# md-01.net
KiCad netlist of a schematic drawn in EAGLE
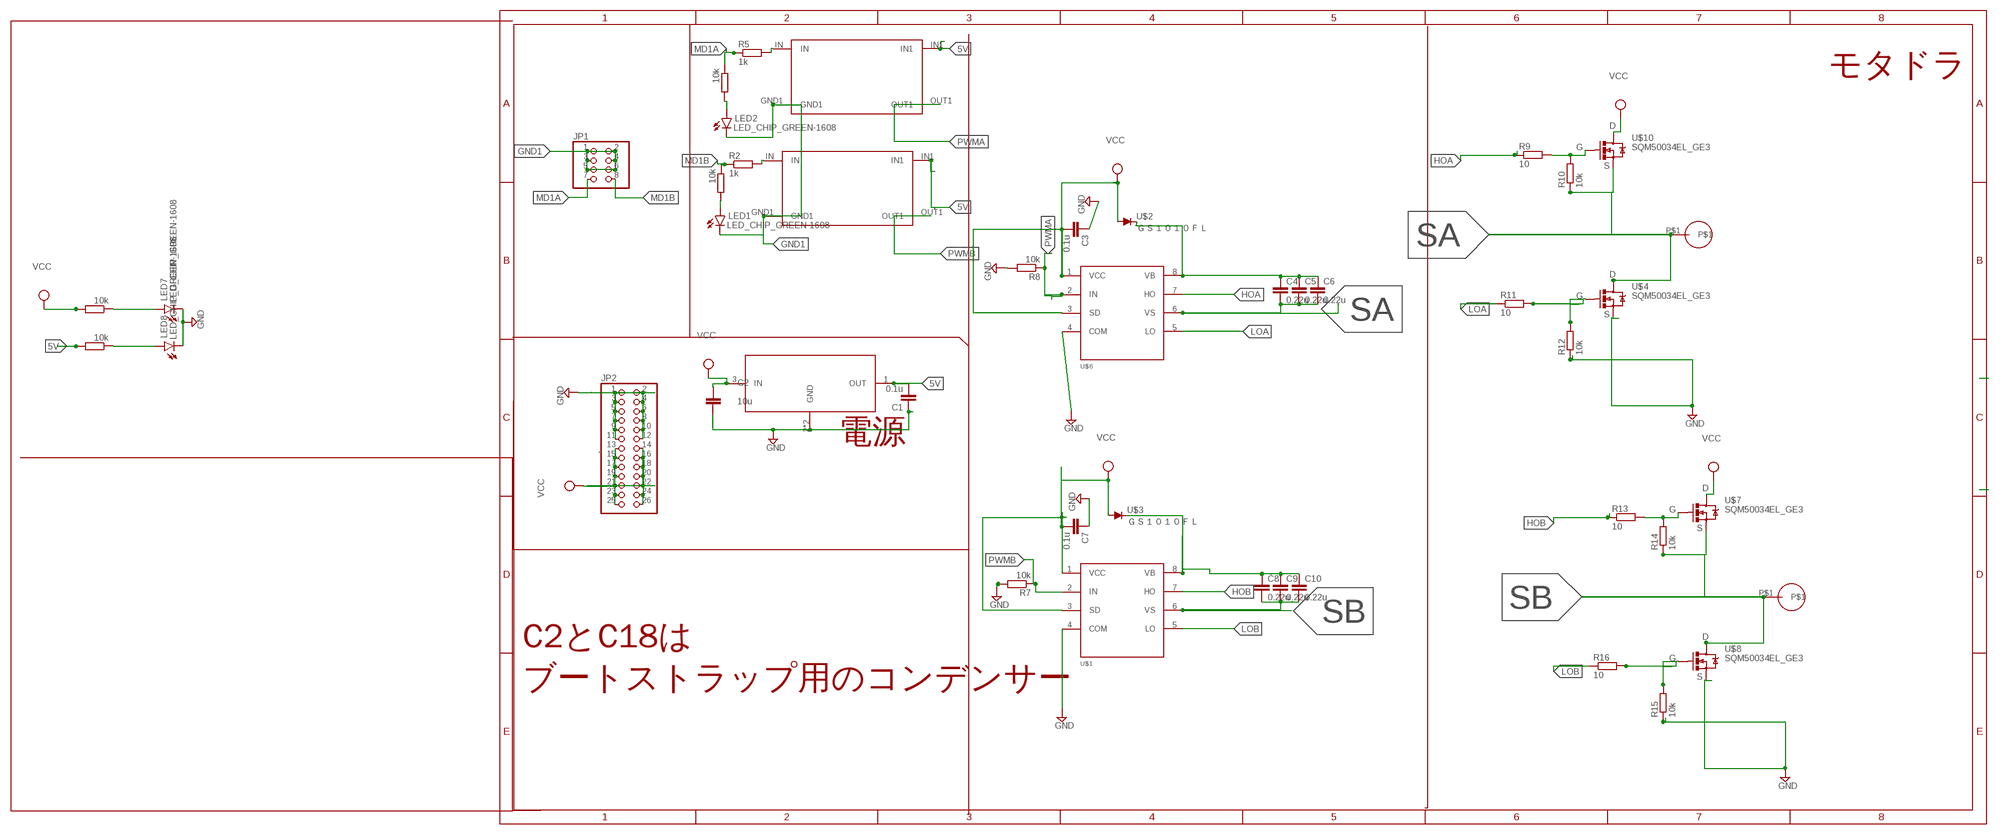
[diagram p0: schematic, sheet 1]

(export (version "E")
  (design (tool "Eeschema 10.0.6"))
  (components
    (comp (ref "C1")
      (value "0.1u")
      (footprint "eagle-import:C0603")
      (libsource (lib "eagle-import") (part "C-EUC0603"))
    )
    (comp (ref "C2")
      (value "10u")
      (footprint "eagle-import:C0805")
      (libsource (lib "eagle-import") (part "C-EUC0805"))
    )
    (comp (ref "C3")
      (value "0.1u")
      (footprint "eagle-import:C0603")
      (libsource (lib "eagle-import") (part "C-EUC0603"))
    )
    (comp (ref "C4")
      (value "0.22u")
      (footprint "eagle-import:C2012")
      (libsource (lib "eagle-import") (part "C-EUC2012"))
    )
    (comp (ref "C5")
      (value "0.22u")
      (footprint "eagle-import:C2012")
      (libsource (lib "eagle-import") (part "C-EUC2012"))
    )
    (comp (ref "C6")
      (value "0.22u")
      (footprint "eagle-import:C2012")
      (libsource (lib "eagle-import") (part "C-EUC2012"))
    )
    (comp (ref "C7")
      (value "0.1u")
      (footprint "eagle-import:C0603")
      (libsource (lib "eagle-import") (part "C-EUC0603"))
    )
    (comp (ref "C8")
      (value "0.22u")
      (footprint "eagle-import:C2012")
      (libsource (lib "eagle-import") (part "C-EUC2012"))
    )
    (comp (ref "C9")
      (value "0.22u")
      (footprint "eagle-import:C2012")
      (libsource (lib "eagle-import") (part "C-EUC2012"))
    )
    (comp (ref "C10")
      (value "0.22u")
      (footprint "eagle-import:C2012")
      (libsource (lib "eagle-import") (part "C-EUC2012"))
    )
    (comp (ref "JP1")
      (value "PINHD-2X4/90")
      (footprint "eagle-import:2X04_90")
      (libsource (lib "eagle-import") (part "PINHD-2X4/90"))
    )
    (comp (ref "JP2")
      (value "PINHD-2X13/90")
      (footprint "eagle-import:2X13_90")
      (libsource (lib "eagle-import") (part "PINHD-2X13/90"))
    )
    (comp (ref "LED1")
      (value "LED_CHIP_GREEN-1608")
      (footprint "eagle-import:LEDC1608X39N_G")
      (libsource (lib "eagle-import") (part "LED_CHIPGREEN-1608_"))
    )
    (comp (ref "LED2")
      (value "LED_CHIP_GREEN-1608")
      (footprint "eagle-import:LEDC1608X39N_G")
      (libsource (lib "eagle-import") (part "LED_CHIPGREEN-1608_"))
    )
    (comp (ref "LED7")
      (value "LED_CHIP_GREEN-1608")
      (footprint "eagle-import:LEDC1608X39N_G")
      (libsource (lib "eagle-import") (part "LED_CHIPGREEN-1608_"))
    )
    (comp (ref "LED8")
      (value "LED_CHIP_GREEN-1608")
      (footprint "eagle-import:LEDC1608X39N_G")
      (libsource (lib "eagle-import") (part "LED_CHIPGREEN-1608_"))
    )
    (comp (ref "R1")
      (value "10k")
      (footprint "eagle-import:R0603")
      (libsource (lib "eagle-import") (part "R-EU_R0603"))
    )
    (comp (ref "R2")
      (value "1k")
      (footprint "eagle-import:R0603")
      (libsource (lib "eagle-import") (part "R-EU_R0603"))
    )
    (comp (ref "R4")
      (value "10k")
      (footprint "eagle-import:R0603")
      (libsource (lib "eagle-import") (part "R-EU_R0603"))
    )
    (comp (ref "R5")
      (value "1k")
      (footprint "eagle-import:R0603")
      (libsource (lib "eagle-import") (part "R-EU_R0603"))
    )
    (comp (ref "R7")
      (value "10k")
      (footprint "eagle-import:R0603")
      (libsource (lib "eagle-import") (part "R-EU_R0603"))
    )
    (comp (ref "R8")
      (value "10k")
      (footprint "eagle-import:R0603")
      (libsource (lib "eagle-import") (part "R-EU_R0603"))
    )
    (comp (ref "R9")
      (value "10")
      (footprint "eagle-import:R0603")
      (libsource (lib "eagle-import") (part "R-EU_R0603"))
    )
    (comp (ref "R10")
      (value "10k")
      (footprint "eagle-import:R0603")
      (libsource (lib "eagle-import") (part "R-EU_R0603"))
    )
    (comp (ref "R11")
      (value "10")
      (footprint "eagle-import:R0603")
      (libsource (lib "eagle-import") (part "R-EU_R0603"))
    )
    (comp (ref "R12")
      (value "10k")
      (footprint "eagle-import:R0603")
      (libsource (lib "eagle-import") (part "R-EU_R0603"))
    )
    (comp (ref "R13")
      (value "10")
      (footprint "eagle-import:R0603")
      (libsource (lib "eagle-import") (part "R-EU_R0603"))
    )
    (comp (ref "R14")
      (value "10k")
      (footprint "eagle-import:R0603")
      (libsource (lib "eagle-import") (part "R-EU_R0603"))
    )
    (comp (ref "R15")
      (value "10k")
      (footprint "eagle-import:R0603")
      (libsource (lib "eagle-import") (part "R-EU_R0603"))
    )
    (comp (ref "R16")
      (value "10")
      (footprint "eagle-import:R0603")
      (libsource (lib "eagle-import") (part "R-EU_R0603"))
    )
    (comp (ref "R17")
      (value "10k")
      (footprint "eagle-import:R0603")
      (libsource (lib "eagle-import") (part "R-EU_R0603"))
    )
    (comp (ref "R19")
      (value "10k")
      (footprint "eagle-import:R0603")
      (libsource (lib "eagle-import") (part "R-EU_R0603"))
    )
    (comp (ref "U$1")
      (value "ＩＲ２１０４ＳＴＲＰＢＦ")
      (footprint "eagle-import:SOIC-8")
      (libsource (lib "eagle-import") (part "ＩＲ２１０４ＳＴＲＰＢＦ"))
    )
    (comp (ref "U$2")
      (value "ＧＳ１０１０ＦＬ")
      (footprint "eagle-import:DIODE_SOD-123FL")
      (libsource (lib "eagle-import") (part "ＧＳ１０１０ＦＬ"))
    )
    (comp (ref "U$3")
      (value "ＧＳ１０１０ＦＬ")
      (footprint "eagle-import:DIODE_SOD-123FL")
      (libsource (lib "eagle-import") (part "ＧＳ１０１０ＦＬ"))
    )
    (comp (ref "U$4")
      (value "SQM50034EL_GE3")
      (footprint "eagle-import:TO-263_D2PAK")
      (libsource (lib "eagle-import") (part "SQM50034EL_GE3"))
    )
    (comp (ref "U$5")
      (value "PV-3")
      (footprint "eagle-import:PV-3")
      (libsource (lib "eagle-import") (part "PV-3"))
    )
    (comp (ref "U$6")
      (value "ＩＲ２１０４ＳＴＲＰＢＦ")
      (footprint "eagle-import:SOIC-8")
      (libsource (lib "eagle-import") (part "ＩＲ２１０４ＳＴＲＰＢＦ"))
    )
    (comp (ref "U$7")
      (value "SQM50034EL_GE3")
      (footprint "eagle-import:TO-263_D2PAK")
      (libsource (lib "eagle-import") (part "SQM50034EL_GE3"))
    )
    (comp (ref "U$8")
      (value "SQM50034EL_GE3")
      (footprint "eagle-import:TO-263_D2PAK")
      (libsource (lib "eagle-import") (part "SQM50034EL_GE3"))
    )
    (comp (ref "U$9")
      (value "PV-3")
      (footprint "eagle-import:PV-3")
      (libsource (lib "eagle-import") (part "PV-3"))
    )
    (comp (ref "U$10")
      (value "SQM50034EL_GE3")
      (footprint "eagle-import:TO-263_D2PAK")
      (libsource (lib "eagle-import") (part "SQM50034EL_GE3"))
    )
    (comp (ref "U$11")
      (value "ＴＬＰ２９３（ＧＢ）")
      (footprint "eagle-import:MINI-FLAT-4")
      (libsource (lib "eagle-import") (part "ＴＬＰ２９３（ＧＢ）"))
    )
    (comp (ref "U$12")
      (value "ＴＬＰ２９３（ＧＢ）")
      (footprint "eagle-import:MINI-FLAT-4")
      (libsource (lib "eagle-import") (part "ＴＬＰ２９３（ＧＢ）"))
    )
    (comp (ref "U$13")
      (value "NJM78L05SU3")
      (footprint "eagle-import:SOT-89")
      (libsource (lib "eagle-import") (part "NJM78L05SU3"))
    )
  )
  (nets
    (net (code "1") (name "5V") (class "Default")
      (node (ref "C1") (pin "2") (pinfunction "2_2") (pintype "passive"))
      (node (ref "R19") (pin "2") (pinfunction "2_2") (pintype "passive"))
      (node (ref "U$11") (pin "IN1") (pinfunction "IN1_IN1") (pintype "bidirectional"))
      (node (ref "U$12") (pin "IN1") (pinfunction "IN1_IN1") (pintype "bidirectional"))
      (node (ref "U$13") (pin "1") (pinfunction "OUT_1") (pintype "bidirectional"))
    )
    (net (code "2") (name "GND") (class "Default")
      (node (ref "C1") (pin "1") (pinfunction "1_1") (pintype "passive"))
      (node (ref "C2") (pin "2") (pinfunction "2_2") (pintype "passive"))
      (node (ref "C3") (pin "1") (pinfunction "1_1") (pintype "passive"))
      (node (ref "C7") (pin "1") (pinfunction "1_1") (pintype "passive"))
      (node (ref "JP2") (pin "1") (pinfunction "1_1") (pintype "passive"))
      (node (ref "JP2") (pin "10") (pinfunction "10_10") (pintype "passive"))
      (node (ref "JP2") (pin "11") (pinfunction "11_11") (pintype "passive"))
      (node (ref "JP2") (pin "12") (pinfunction "12_12") (pintype "passive"))
      (node (ref "JP2") (pin "2") (pinfunction "2_2") (pintype "passive"))
      (node (ref "JP2") (pin "3") (pinfunction "3_3") (pintype "passive"))
      (node (ref "JP2") (pin "4") (pinfunction "4_4") (pintype "passive"))
      (node (ref "JP2") (pin "5") (pinfunction "5_5") (pintype "passive"))
      (node (ref "JP2") (pin "6") (pinfunction "6_6") (pintype "passive"))
      (node (ref "JP2") (pin "7") (pinfunction "7_7") (pintype "passive"))
      (node (ref "JP2") (pin "8") (pinfunction "8_8") (pintype "passive"))
      (node (ref "JP2") (pin "9") (pinfunction "9_9") (pintype "passive"))
      (node (ref "LED7") (pin "1") (pinfunction "C_1") (pintype "passive"))
      (node (ref "LED8") (pin "1") (pinfunction "C_1") (pintype "passive"))
      (node (ref "R12") (pin "1") (pinfunction "1_1") (pintype "passive"))
      (node (ref "R15") (pin "1") (pinfunction "1_1") (pintype "passive"))
      (node (ref "R7") (pin "2") (pinfunction "2_2") (pintype "passive"))
      (node (ref "R8") (pin "2") (pinfunction "2_2") (pintype "passive"))
      (node (ref "U$1") (pin "4") (pinfunction "COM_4") (pintype "bidirectional"))
      (node (ref "U$13") (pin "2") (pinfunction "GND_2") (pintype "bidirectional"))
      (node (ref "U$13") (pin "4") (pinfunction "GND_4") (pintype "bidirectional"))
      (node (ref "U$4") (pin "S") (pinfunction "S_S") (pintype "passive"))
      (node (ref "U$6") (pin "4") (pinfunction "COM_4") (pintype "bidirectional"))
      (node (ref "U$8") (pin "S") (pinfunction "S_S") (pintype "passive"))
    )
    (net (code "3") (name "GND1") (class "Default")
      (node (ref "JP1") (pin "1") (pinfunction "1_1") (pintype "passive"))
      (node (ref "JP1") (pin "2") (pinfunction "2_2") (pintype "passive"))
      (node (ref "JP1") (pin "3") (pinfunction "3_3") (pintype "passive"))
      (node (ref "JP1") (pin "4") (pinfunction "4_4") (pintype "passive"))
      (node (ref "JP1") (pin "5") (pinfunction "5_5") (pintype "passive"))
      (node (ref "JP1") (pin "6") (pinfunction "6_6") (pintype "passive"))
      (node (ref "LED1") (pin "1") (pinfunction "C_1") (pintype "passive"))
      (node (ref "LED2") (pin "1") (pinfunction "C_1") (pintype "passive"))
      (node (ref "U$11") (pin "GND1") (pinfunction "GND1_GND1") (pintype "bidirectional"))
      (node (ref "U$12") (pin "GND1") (pinfunction "GND1_GND1") (pintype "bidirectional"))
    )
    (net (code "4") (name "HOA") (class "Default")
      (node (ref "R9") (pin "1") (pinfunction "1_1") (pintype "passive"))
      (node (ref "U$6") (pin "7") (pinfunction "HO_7") (pintype "bidirectional"))
    )
    (net (code "5") (name "HOB") (class "Default")
      (node (ref "R13") (pin "1") (pinfunction "1_1") (pintype "passive"))
      (node (ref "U$1") (pin "7") (pinfunction "HO_7") (pintype "bidirectional"))
    )
    (net (code "6") (name "LOA") (class "Default")
      (node (ref "R11") (pin "1") (pinfunction "1_1") (pintype "passive"))
      (node (ref "U$6") (pin "5") (pinfunction "LO_5") (pintype "bidirectional"))
    )
    (net (code "7") (name "LOB") (class "Default")
      (node (ref "R16") (pin "1") (pinfunction "1_1") (pintype "passive"))
      (node (ref "U$1") (pin "5") (pinfunction "LO_5") (pintype "bidirectional"))
    )
    (net (code "8") (name "MD1A") (class "Default")
      (node (ref "JP1") (pin "7") (pinfunction "7_7") (pintype "passive"))
      (node (ref "R4") (pin "1") (pinfunction "1_1") (pintype "passive"))
      (node (ref "R5") (pin "1") (pinfunction "1_1") (pintype "passive"))
    )
    (net (code "9") (name "MD1B") (class "Default")
      (node (ref "JP1") (pin "8") (pinfunction "8_8") (pintype "passive"))
      (node (ref "R1") (pin "1") (pinfunction "1_1") (pintype "passive"))
      (node (ref "R2") (pin "1") (pinfunction "1_1") (pintype "passive"))
    )
    (net (code "10") (name "Net-(LED1-A)") (class "Default")
      (node (ref "LED1") (pin "2") (pinfunction "A_2") (pintype "passive"))
      (node (ref "R1") (pin "2") (pinfunction "2_2") (pintype "passive"))
    )
    (net (code "11") (name "Net-(LED2-A)") (class "Default")
      (node (ref "LED2") (pin "2") (pinfunction "A_2") (pintype "passive"))
      (node (ref "R4") (pin "2") (pinfunction "2_2") (pintype "passive"))
    )
    (net (code "12") (name "Net-(LED7-A)") (class "Default")
      (node (ref "LED7") (pin "2") (pinfunction "A_2") (pintype "passive"))
      (node (ref "R17") (pin "1") (pinfunction "1_1") (pintype "passive"))
    )
    (net (code "13") (name "Net-(LED8-A)") (class "Default")
      (node (ref "LED8") (pin "2") (pinfunction "A_2") (pintype "passive"))
      (node (ref "R19") (pin "1") (pinfunction "1_1") (pintype "passive"))
    )
    (net (code "14") (name "Net-(R2-Pad2)") (class "Default")
      (node (ref "R2") (pin "2") (pinfunction "2_2") (pintype "passive"))
      (node (ref "U$12") (pin "IN") (pinfunction "IN_IN") (pintype "bidirectional"))
    )
    (net (code "15") (name "Net-(R5-Pad2)") (class "Default")
      (node (ref "R5") (pin "2") (pinfunction "2_2") (pintype "passive"))
      (node (ref "U$11") (pin "IN") (pinfunction "IN_IN") (pintype "bidirectional"))
    )
    (net (code "16") (name "Net-(R10-Pad2)") (class "Default")
      (node (ref "R10") (pin "2") (pinfunction "2_2") (pintype "passive"))
      (node (ref "R9") (pin "2") (pinfunction "2_2") (pintype "passive"))
      (node (ref "U$10") (pin "G") (pinfunction "G_G") (pintype "passive"))
    )
    (net (code "17") (name "Net-(R11-Pad2)") (class "Default")
      (node (ref "R11") (pin "2") (pinfunction "2_2") (pintype "passive"))
      (node (ref "R12") (pin "2") (pinfunction "2_2") (pintype "passive"))
      (node (ref "U$4") (pin "G") (pinfunction "G_G") (pintype "passive"))
    )
    (net (code "18") (name "Net-(R13-Pad2)") (class "Default")
      (node (ref "R13") (pin "2") (pinfunction "2_2") (pintype "passive"))
      (node (ref "R14") (pin "2") (pinfunction "2_2") (pintype "passive"))
      (node (ref "U$7") (pin "G") (pinfunction "G_G") (pintype "passive"))
    )
    (net (code "19") (name "Net-(R15-Pad2)") (class "Default")
      (node (ref "R15") (pin "2") (pinfunction "2_2") (pintype "passive"))
      (node (ref "R16") (pin "2") (pinfunction "2_2") (pintype "passive"))
      (node (ref "U$8") (pin "G") (pinfunction "G_G") (pintype "passive"))
    )
    (net (code "20") (name "Net-(U$1-VB)") (class "Default")
      (node (ref "C10") (pin "1") (pinfunction "1_1") (pintype "passive"))
      (node (ref "C8") (pin "1") (pinfunction "1_1") (pintype "passive"))
      (node (ref "C9") (pin "1") (pinfunction "1_1") (pintype "passive"))
      (node (ref "U$1") (pin "8") (pinfunction "VB_8") (pintype "bidirectional"))
      (node (ref "U$3") (pin "C") (pinfunction "C_C") (pintype "passive"))
    )
    (net (code "21") (name "Net-(U$6-VB)") (class "Default")
      (node (ref "C4") (pin "1") (pinfunction "1_1") (pintype "passive"))
      (node (ref "C5") (pin "1") (pinfunction "1_1") (pintype "passive"))
      (node (ref "C6") (pin "1") (pinfunction "1_1") (pintype "passive"))
      (node (ref "U$2") (pin "C") (pinfunction "C_C") (pintype "passive"))
      (node (ref "U$6") (pin "8") (pinfunction "VB_8") (pintype "bidirectional"))
    )
    (net (code "22") (name "PWMA") (class "Default")
      (node (ref "R8") (pin "1") (pinfunction "1_1") (pintype "passive"))
      (node (ref "U$11") (pin "OUT1") (pinfunction "OUT1_OUT1") (pintype "bidirectional"))
      (node (ref "U$6") (pin "2") (pinfunction "IN_2") (pintype "bidirectional"))
    )
    (net (code "23") (name "PWMB") (class "Default")
      (node (ref "R7") (pin "1") (pinfunction "1_1") (pintype "passive"))
      (node (ref "U$1") (pin "2") (pinfunction "IN_2") (pintype "bidirectional"))
      (node (ref "U$12") (pin "OUT1") (pinfunction "OUT1_OUT1") (pintype "bidirectional"))
    )
    (net (code "24") (name "SA") (class "Default")
      (node (ref "C4") (pin "2") (pinfunction "2_2") (pintype "passive"))
      (node (ref "C5") (pin "2") (pinfunction "2_2") (pintype "passive"))
      (node (ref "C6") (pin "2") (pinfunction "2_2") (pintype "passive"))
      (node (ref "R10") (pin "1") (pinfunction "1_1") (pintype "passive"))
      (node (ref "U$10") (pin "S") (pinfunction "S_S") (pintype "passive"))
      (node (ref "U$4") (pin "D") (pinfunction "D_D") (pintype "passive"))
      (node (ref "U$6") (pin "6") (pinfunction "VS_6") (pintype "bidirectional"))
      (node (ref "U$9") (pin "P$1") (pinfunction "P$1_P$1") (pintype "bidirectional"))
    )
    (net (code "25") (name "SB") (class "Default")
      (node (ref "C10") (pin "2") (pinfunction "2_2") (pintype "passive"))
      (node (ref "C8") (pin "2") (pinfunction "2_2") (pintype "passive"))
      (node (ref "C9") (pin "2") (pinfunction "2_2") (pintype "passive"))
      (node (ref "R14") (pin "1") (pinfunction "1_1") (pintype "passive"))
      (node (ref "U$1") (pin "6") (pinfunction "VS_6") (pintype "bidirectional"))
      (node (ref "U$5") (pin "P$1") (pinfunction "P$1_P$1") (pintype "bidirectional"))
      (node (ref "U$7") (pin "S") (pinfunction "S_S") (pintype "passive"))
      (node (ref "U$8") (pin "D") (pinfunction "D_D") (pintype "passive"))
    )
    (net (code "26") (name "VCC") (class "Default")
      (node (ref "C2") (pin "1") (pinfunction "1_1") (pintype "passive"))
      (node (ref "C3") (pin "2") (pinfunction "2_2") (pintype "passive"))
      (node (ref "C7") (pin "2") (pinfunction "2_2") (pintype "passive"))
      (node (ref "JP2") (pin "13") (pinfunction "13_13") (pintype "passive"))
      (node (ref "JP2") (pin "14") (pinfunction "14_14") (pintype "passive"))
      (node (ref "JP2") (pin "15") (pinfunction "15_15") (pintype "passive"))
      (node (ref "JP2") (pin "16") (pinfunction "16_16") (pintype "passive"))
      (node (ref "JP2") (pin "17") (pinfunction "17_17") (pintype "passive"))
      (node (ref "JP2") (pin "18") (pinfunction "18_18") (pintype "passive"))
      (node (ref "JP2") (pin "19") (pinfunction "19_19") (pintype "passive"))
      (node (ref "JP2") (pin "20") (pinfunction "20_20") (pintype "passive"))
      (node (ref "JP2") (pin "21") (pinfunction "21_21") (pintype "passive"))
      (node (ref "JP2") (pin "22") (pinfunction "22_22") (pintype "passive"))
      (node (ref "JP2") (pin "23") (pinfunction "23_23") (pintype "passive"))
      (node (ref "JP2") (pin "24") (pinfunction "24_24") (pintype "passive"))
      (node (ref "JP2") (pin "25") (pinfunction "25_25") (pintype "passive"))
      (node (ref "JP2") (pin "26") (pinfunction "26_26") (pintype "passive"))
      (node (ref "R17") (pin "2") (pinfunction "2_2") (pintype "passive"))
      (node (ref "U$1") (pin "1") (pinfunction "VCC_1") (pintype "bidirectional"))
      (node (ref "U$1") (pin "3") (pinfunction "SD_3") (pintype "bidirectional"))
      (node (ref "U$10") (pin "D") (pinfunction "D_D") (pintype "passive"))
      (node (ref "U$13") (pin "3") (pinfunction "IN_3") (pintype "bidirectional"))
      (node (ref "U$2") (pin "A") (pinfunction "A_A") (pintype "passive"))
      (node (ref "U$3") (pin "A") (pinfunction "A_A") (pintype "passive"))
      (node (ref "U$6") (pin "1") (pinfunction "VCC_1") (pintype "bidirectional"))
      (node (ref "U$6") (pin "3") (pinfunction "SD_3") (pintype "bidirectional"))
      (node (ref "U$7") (pin "D") (pinfunction "D_D") (pintype "passive"))
    )
  )
)
